# Umbilical_eFuse.net
KiCad netlist of a schematic drawn in Altium Designer
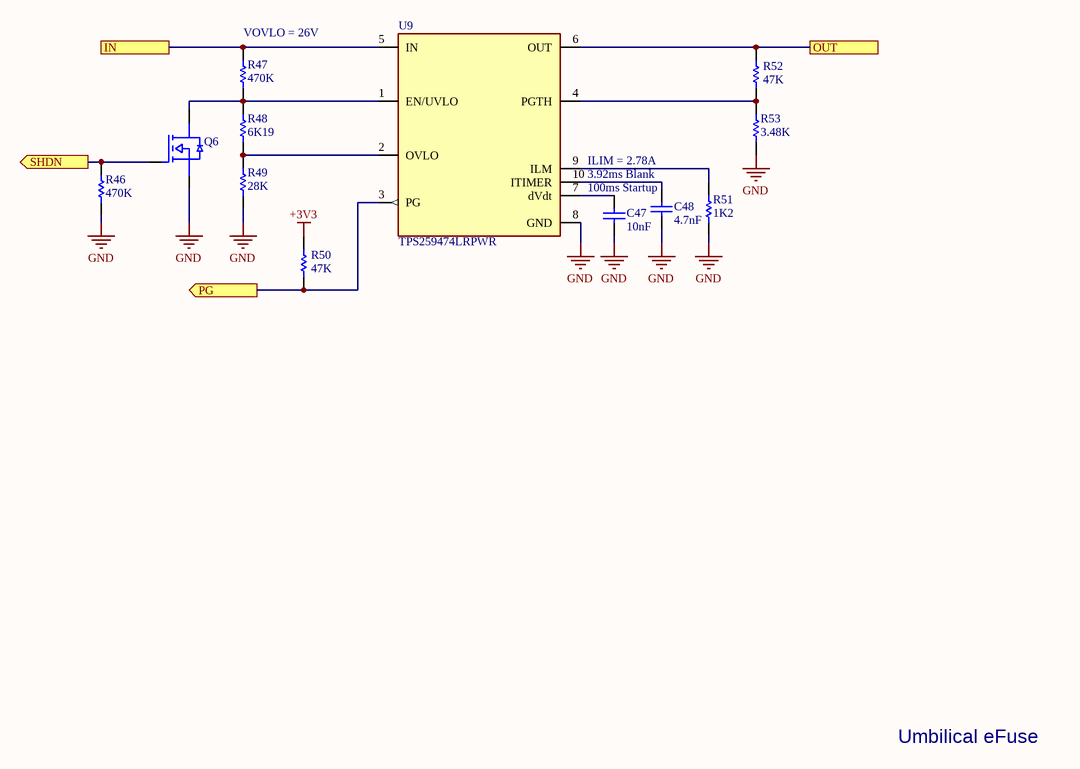
[diagram p0: Umbilical_eFuse.SchDoc]

(export (version "E")
  (design (tool "Eeschema 10.0.6"))
  (components
    (comp (ref "C47")
      (value "CL10B103KB8NNNC")
      (footprint "CAPC0603X060")
      (description "10nF ±10% 50V Ceramic Capacitor X7R 0603 (1608 Metric)")
      (fields
        (field (name "DISTRIBUTOR PART NUMBER") "1276-1009-1-ND")
        (field (name "TOLERANCE") "10%")
        (field (name "CAPACITANCE") "10nF")
      )
      (libsource (lib "Ahristi_Library") (part "CL10B103KB8NNNC"))
    )
    (comp (ref "C48")
      (value "C0603C472K4RECAUTO")
      (footprint "CAPC0603X040")
      (description "4.7nF ±10% 16V Ceramic Capacitor X7R 0603 (1608 Metric)")
      (fields
        (field (name "TOLERANCE") "10%")
        (field (name "DISTRIBUTOR PART NUMBER") "399-17879-1-ND")
        (field (name "CAPACITANCE") "4.7nF")
      )
      (libsource (lib "Ahristi_Library") (part "C0603C472K4RECAUTO"))
    )
    (comp (ref "Q6")
      (value "T2N7002AK,LM")
      (footprint "SOT23-3 MOSFET")
      (description "N-Channel 60 V 200mA (Ta) 320mW (Ta) Surface Mount SOT-23-3")
      (fields (field (name "DISTRIBUTOR PART NUMBER") "T2N7002AKLMCT-ND"))
      (libsource (lib "Ahristi_Library") (part "T2N7002AK,LM"))
    )
    (comp (ref "R46")
      (value "RMCF0603FT470K")
      (footprint "RESC0603")
      (description "470 kOhms ±1% 0.1W, 1/10W Chip Resistor 0603 (1608 Metric) Automotive AEC-Q200 Thick Film")
      (fields
        (field (name "TOLERANCE") "1%")
        (field (name "DISTRIBUTOR PART NUMBER") "RMCF0603FT470KCT-ND")
        (field (name "RESISTANCE") "470K")
      )
      (libsource (lib "Ahristi_Library") (part "RMCF0603FT470K"))
    )
    (comp (ref "R47")
      (value "RMCF0603FT470K")
      (footprint "RESC0603")
      (description "470 kOhms ±1% 0.1W, 1/10W Chip Resistor 0603 (1608 Metric) Automotive AEC-Q200 Thick Film")
      (fields
        (field (name "TOLERANCE") "1%")
        (field (name "DISTRIBUTOR PART NUMBER") "RMCF0603FT470KCT-ND")
        (field (name "RESISTANCE") "470K")
      )
      (libsource (lib "Ahristi_Library") (part "RMCF0603FT470K"))
    )
    (comp (ref "R48")
      (value "RMCF0603FT6K19")
      (footprint "RESC0603")
      (description "6.19 kOhms ±1% 0.1W, 1/10W Chip Resistor 0603 (1608 Metric) Automotive AEC-Q200 Thick Film")
      (fields
        (field (name "TOLERANCE") "1%")
        (field (name "DISTRIBUTOR PART NUMBER") "RMCF0603FT6K19CT-ND")
        (field (name "RESISTANCE") "6K19")
      )
      (libsource (lib "Ahristi_Library") (part "RMCF0603FT6K19"))
    )
    (comp (ref "R49")
      (value "RMCF0603FT28K0")
      (footprint "RESC0603")
      (description "28 kOhms ±1% 0.1W, 1/10W Chip Resistor 0603 (1608 Metric) Automotive AEC-Q200 Thick Film")
      (fields
        (field (name "TOLERANCE") "1%")
        (field (name "DISTRIBUTOR PART NUMBER") "RMCF0603FT28K0CT-ND")
        (field (name "RESISTANCE") "28K")
      )
      (libsource (lib "Ahristi_Library") (part "RMCF0603FT28K0"))
    )
    (comp (ref "R50")
      (value "RMCF0603FT47K0")
      (footprint "RESC0603")
      (description "47 kOhms ±1% 0.1W, 1/10W Chip Resistor 0603 (1608 Metric) Automotive AEC-Q200 Thick Film")
      (fields
        (field (name "TOLERANCE") "1%")
        (field (name "DISTRIBUTOR PART NUMBER") "RMCF0603FT47K0CT-ND")
        (field (name "RESISTANCE") "47K")
      )
      (libsource (lib "Ahristi_Library") (part "RMCF0603FT47K0"))
    )
    (comp (ref "R51")
      (value "RMCF0603FT1K2")
      (footprint "RESC0603")
      (description "1.2 kOhms ±1% 0.1W, 1/10W Chip Resistor 0603 (1608 Metric) Automotive AEC-Q200 Thick Film")
      (fields
        (field (name "TOLERANCE") "1%")
        (field (name "DISTRIBUTOR PART NUMBER") "RMCF0603FT1K20CT-ND")
        (field (name "RESISTANCE") "1K2")
      )
      (libsource (lib "Ahristi_Library") (part "RMCF0603FT1K2"))
    )
    (comp (ref "R52")
      (value "RMCF0603FT47K0")
      (footprint "RESC0603")
      (description "47 kOhms ±1% 0.1W, 1/10W Chip Resistor 0603 (1608 Metric) Automotive AEC-Q200 Thick Film")
      (fields
        (field (name "TOLERANCE") "1%")
        (field (name "DISTRIBUTOR PART NUMBER") "RMCF0603FT47K0CT-ND")
        (field (name "RESISTANCE") "47K")
      )
      (libsource (lib "Ahristi_Library") (part "RMCF0603FT47K0"))
    )
    (comp (ref "R53")
      (value "RMCF0603FT3K48")
      (footprint "RESC0603")
      (description "3.48 kOhms ±1% 0.1W, 1/10W Chip Resistor 0603 (1608 Metric) Automotive AEC-Q200 Thick Film")
      (fields
        (field (name "TOLERANCE") "1%")
        (field (name "DISTRIBUTOR PART NUMBER") "RMCF0603FT3K48CT-ND")
        (field (name "RESISTANCE") "3.48K")
      )
      (libsource (lib "Ahristi_Library") (part "RMCF0603FT3K48"))
    )
    (comp (ref "U9")
      (value "TPS259474LRPWR")
      (footprint "VFQFN-10")
      (description "eFuse 5.5A, 2.7V~23V, 28mOhm, Reverse Current Blocking with Input Reverse Polarity Protection")
      (fields (field (name "DISTRIBUTOR PART NUMBER") "296-TPS259474LRPWRCT-ND"))
      (libsource (lib "Ahristi_Library") (part "TPS259474LRPWR"))
    )
  )
  (nets
    (net (code "1") (name "+3V3") (class "Default")
      (node (ref "R50") (pin "2") (pinfunction "2_2") (pintype "passive"))
    )
    (net (code "2") (name "/IN") (class "Default")
      (node (ref "R47") (pin "2") (pinfunction "2_2") (pintype "passive"))
      (node (ref "U9") (pin "5") (pinfunction "IN_5") (pintype "passive"))
    )
    (net (code "3") (name "/OUT") (class "Default")
      (node (ref "R52") (pin "2") (pinfunction "2_2") (pintype "passive"))
      (node (ref "U9") (pin "6") (pinfunction "OUT_6") (pintype "passive"))
    )
    (net (code "4") (name "/PG") (class "Default")
      (node (ref "R50") (pin "1") (pinfunction "1_1") (pintype "passive"))
      (node (ref "U9") (pin "3") (pinfunction "PG_3") (pintype "output"))
    )
    (net (code "5") (name "/SHDN") (class "Default")
      (node (ref "Q6") (pin "G") (pinfunction "G_G") (pintype "passive"))
      (node (ref "R46") (pin "2") (pinfunction "2_2") (pintype "passive"))
    )
    (net (code "6") (name "GND") (class "Default")
      (node (ref "C47") (pin "1") (pinfunction "1_1") (pintype "passive"))
      (node (ref "C48") (pin "1") (pinfunction "1_1") (pintype "passive"))
      (node (ref "Q6") (pin "S") (pinfunction "S_S") (pintype "passive"))
      (node (ref "R46") (pin "1") (pinfunction "1_1") (pintype "passive"))
      (node (ref "R49") (pin "1") (pinfunction "1_1") (pintype "passive"))
      (node (ref "R51") (pin "1") (pinfunction "1_1") (pintype "passive"))
      (node (ref "R53") (pin "1") (pinfunction "1_1") (pintype "passive"))
      (node (ref "U9") (pin "8") (pinfunction "GND_8") (pintype "passive"))
    )
    (net (code "7") (name "Net-(U9-EN{slash}UVLO)") (class "Default")
      (node (ref "Q6") (pin "D") (pinfunction "D_D") (pintype "passive"))
      (node (ref "R47") (pin "1") (pinfunction "1_1") (pintype "passive"))
      (node (ref "R48") (pin "2") (pinfunction "2_2") (pintype "passive"))
      (node (ref "U9") (pin "1") (pinfunction "EN/UVLO_1") (pintype "passive"))
    )
    (net (code "8") (name "Net-(U9-ILM)") (class "Default")
      (node (ref "R51") (pin "2") (pinfunction "2_2") (pintype "passive"))
      (node (ref "U9") (pin "9") (pinfunction "ILM_9") (pintype "passive"))
    )
    (net (code "9") (name "Net-(U9-ITIMER)") (class "Default")
      (node (ref "C48") (pin "2") (pinfunction "2_2") (pintype "passive"))
      (node (ref "U9") (pin "10") (pinfunction "ITIMER_10") (pintype "passive"))
    )
    (net (code "10") (name "Net-(U9-OVLO)") (class "Default")
      (node (ref "R48") (pin "1") (pinfunction "1_1") (pintype "passive"))
      (node (ref "R49") (pin "2") (pinfunction "2_2") (pintype "passive"))
      (node (ref "U9") (pin "2") (pinfunction "OVLO_2") (pintype "passive"))
    )
    (net (code "11") (name "Net-(U9-PGTH)") (class "Default")
      (node (ref "R52") (pin "1") (pinfunction "1_1") (pintype "passive"))
      (node (ref "R53") (pin "2") (pinfunction "2_2") (pintype "passive"))
      (node (ref "U9") (pin "4") (pinfunction "PGTH_4") (pintype "passive"))
    )
    (net (code "12") (name "Net-(U9-dVdt)") (class "Default")
      (node (ref "C47") (pin "2") (pinfunction "2_2") (pintype "passive"))
      (node (ref "U9") (pin "7") (pinfunction "dVdt_7") (pintype "passive"))
    )
  )
)
